# PIC24F04KA201_v01.net
KiCad netlist of a schematic drawn in EAGLE
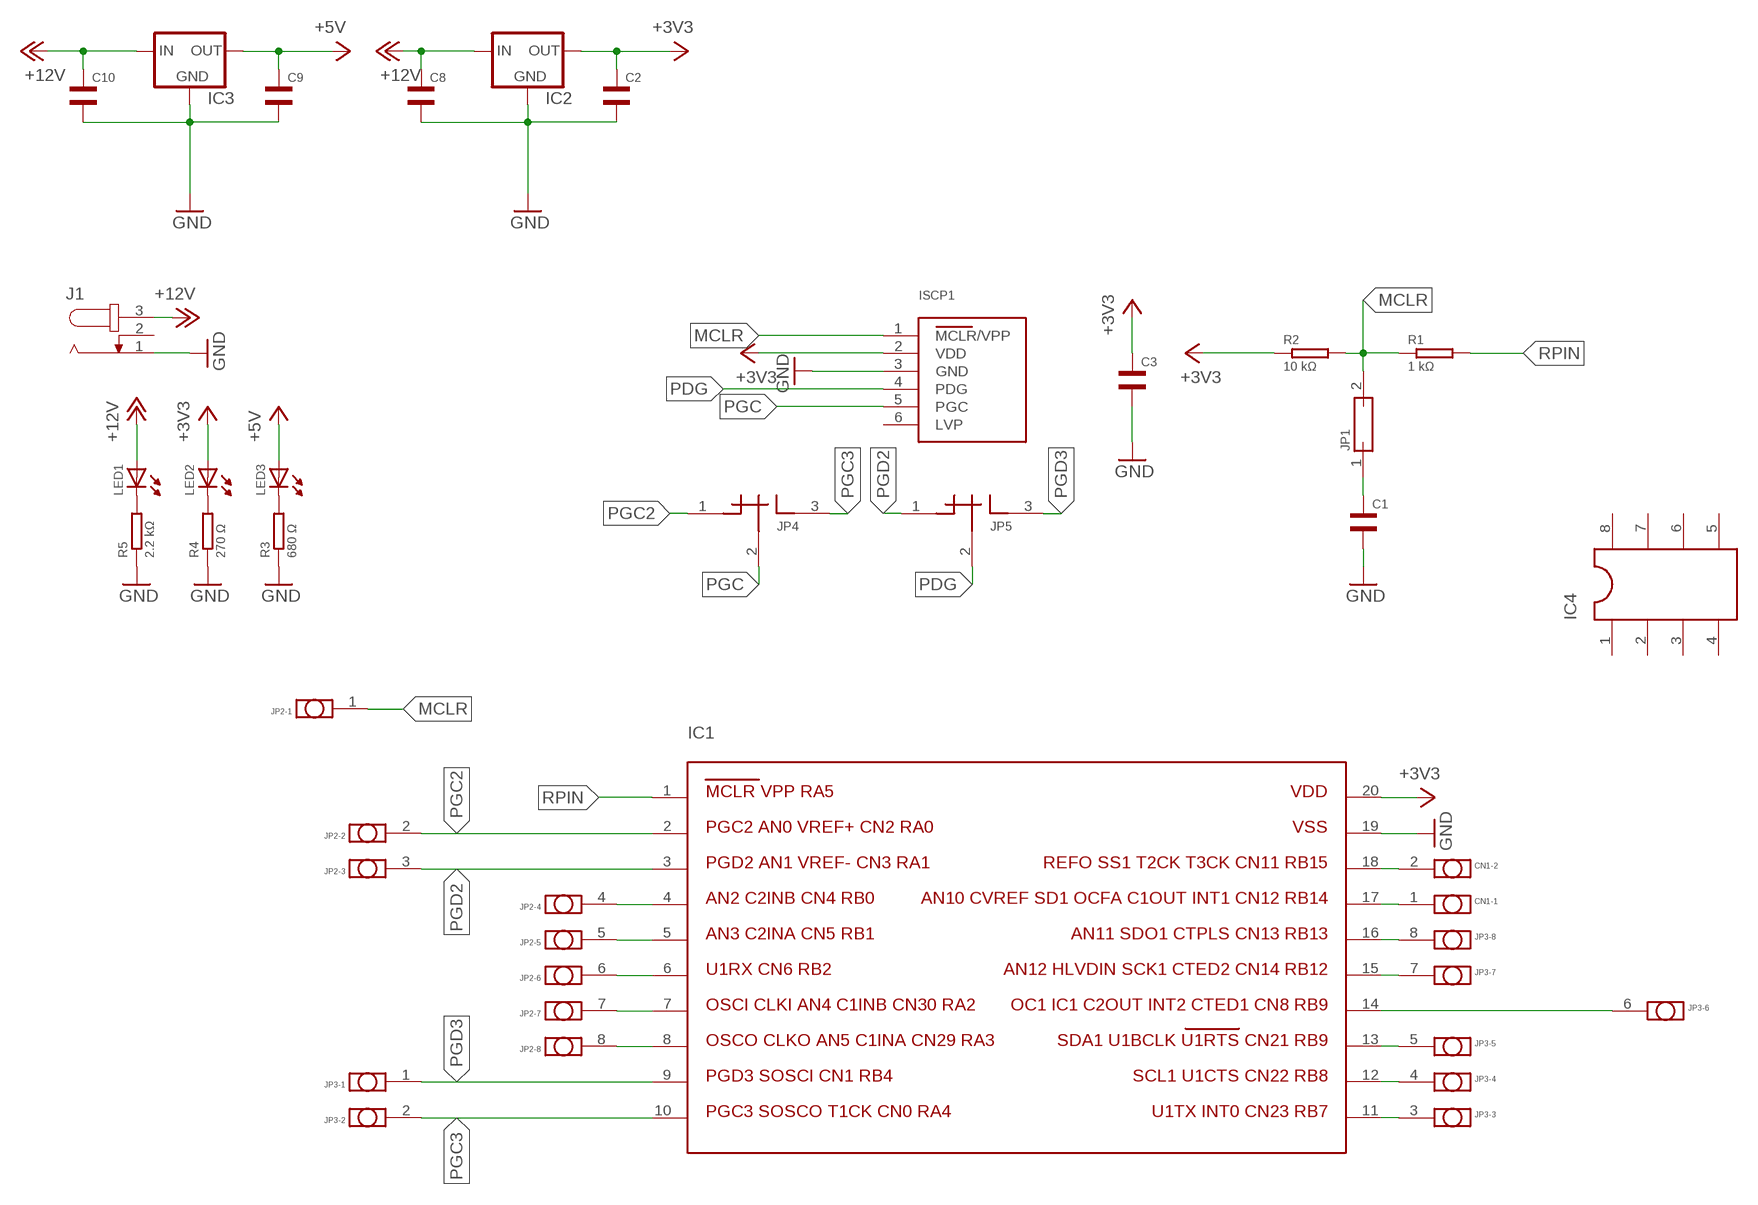
[diagram p0: schematic, sheet 1]

(export (version "E")
  (design (tool "Eeschema 10.0.6"))
  (components
    (comp (ref "C1")
      (value "CAP-SMD-0805")
      (footprint "eagle-import:SMD-0805")
      (libsource (lib "eagle-import") (part "CAP-SMD-0805"))
    )
    (comp (ref "C2")
      (value "CAP-SMD-0805")
      (footprint "eagle-import:SMD-0805")
      (libsource (lib "eagle-import") (part "CAP-SMD-0805"))
    )
    (comp (ref "C3")
      (value "CAP-SMD-0805")
      (footprint "eagle-import:SMD-0805")
      (libsource (lib "eagle-import") (part "CAP-SMD-0805"))
    )
    (comp (ref "C8")
      (value "CAP-SMD-0805")
      (footprint "eagle-import:SMD-0805")
      (libsource (lib "eagle-import") (part "CAP-SMD-0805"))
    )
    (comp (ref "C9")
      (value "CAP-SMD-0805")
      (footprint "eagle-import:SMD-0805")
      (libsource (lib "eagle-import") (part "CAP-SMD-0805"))
    )
    (comp (ref "C10")
      (value "CAP-SMD-0805")
      (footprint "eagle-import:SMD-0805")
      (libsource (lib "eagle-import") (part "CAP-SMD-0805"))
    )
    (comp (ref "CN1")
      (value "1X2")
      (footprint "eagle-import:1X2")
      (libsource (lib "eagle-import") (part "1X2"))
    )
    (comp (ref "IC1")
      (value "PIC24F04KA201")
      (footprint "eagle-import:DIP-20-SOCKET")
      (libsource (lib "eagle-import") (part "PIC24F04KA201"))
    )
    (comp (ref "IC2")
      (value "LD1117V33")
      (footprint "eagle-import:TO-220-STANDING")
      (fields (field (name "MANUFACTURER") "ST Microelectronics"))
      (libsource (lib "eagle-import") (part "LD1117V33"))
    )
    (comp (ref "IC3")
      (value "L78S05CV")
      (footprint "eagle-import:TO-220-STANDING")
      (fields (field (name "MANUFACTURER") "St Microelectronics"))
      (libsource (lib "eagle-import") (part "L78S05CV"))
    )
    (comp (ref "IC4")
      (value "DIP-08S")
      (footprint "eagle-import:DIP-08-SOCKET")
      (libsource (lib "eagle-import") (part "DIP-08S"))
    )
    (comp (ref "ISCP1")
      (value "ICSP1X6-2.54")
      (footprint "eagle-import:1X6-2.54")
      (libsource (lib "eagle-import") (part "ICSP1X6-2.54"))
    )
    (comp (ref "J1")
      (value "JACK-PLUG0")
      (footprint "eagle-import:SPC4077")
      (libsource (lib "eagle-import") (part "JACK-PLUG0"))
    )
    (comp (ref "JP1")
      (value "JP")
      (footprint "eagle-import:1X2")
      (libsource (lib "eagle-import") (part "JP"))
    )
    (comp (ref "JP2")
      (value "1X8")
      (footprint "eagle-import:1X8")
      (libsource (lib "eagle-import") (part "1X8"))
    )
    (comp (ref "JP3")
      (value "1X8")
      (footprint "eagle-import:1X8")
      (libsource (lib "eagle-import") (part "1X8"))
    )
    (comp (ref "JP4")
      (value "JP-OR")
      (footprint "eagle-import:1X3")
      (libsource (lib "eagle-import") (part "JP-OR"))
    )
    (comp (ref "JP5")
      (value "JP-OR")
      (footprint "eagle-import:1X3")
      (libsource (lib "eagle-import") (part "JP-OR"))
    )
    (comp (ref "LED1")
      (value "LED-SMD-0805")
      (footprint "eagle-import:SMD-0805")
      (libsource (lib "eagle-import") (part "LED-SMD-0805"))
    )
    (comp (ref "LED2")
      (value "LED-SMD-0805")
      (footprint "eagle-import:SMD-0805")
      (libsource (lib "eagle-import") (part "LED-SMD-0805"))
    )
    (comp (ref "LED3")
      (value "LED-SMD-0805")
      (footprint "eagle-import:SMD-0805")
      (libsource (lib "eagle-import") (part "LED-SMD-0805"))
    )
    (comp (ref "R1")
      (value "1 kΩ")
      (footprint "eagle-import:SMD-2012(0805)")
      (fields
        (field (name "MANUFACTURER") "Vishay")
        (field (name "POWER") "0.125 W")
        (field (name "TOLERANCE") "1%")
      )
      (libsource (lib "eagle-import") (part "CRCW08051K00FKTABC"))
    )
    (comp (ref "R2")
      (value "10 kΩ")
      (footprint "eagle-import:SMD-2012(0805)")
      (fields
        (field (name "MANUFACTURER") "Vishay")
        (field (name "POWER") "0.125 W")
        (field (name "TOLERANCE") "1%")
      )
      (libsource (lib "eagle-import") (part "CRCW080510K0FKTABC"))
    )
    (comp (ref "R3")
      (value "680 Ω")
      (footprint "eagle-import:SMD-2012(0805)")
      (fields (field (name "POWER") "0.125 W") (field (name "TOLERANCE") "1%"))
      (libsource (lib "eagle-import") (part "CRCW0805680RFKTABC"))
    )
    (comp (ref "R4")
      (value "270 Ω")
      (footprint "eagle-import:SMD-2012(0805)")
      (fields (field (name "POWER") "0.125 W") (field (name "TOLERANCE") "1%"))
      (libsource (lib "eagle-import") (part "CRCW0805270RFKTABC"))
    )
    (comp (ref "R5")
      (value "2.2 kΩ")
      (footprint "eagle-import:SMD-2012(0805)")
      (fields
        (field (name "MANUFACTURER") "Vishay")
        (field (name "POWER") "0.125 W")
        (field (name "TOLERANCE") "1%")
      )
      (libsource (lib "eagle-import") (part "CRCW08052K20FKTABC"))
    )
  )
  (nets
    (net (code "1") (name "+3V3") (class "Default")
      (node (ref "C2") (pin "2") (pinfunction "P$2_2") (pintype "bidirectional"))
      (node (ref "C3") (pin "2") (pinfunction "P$2_2") (pintype "bidirectional"))
      (node (ref "IC1") (pin "20") (pinfunction "P$20_20") (pintype "bidirectional"))
      (node (ref "IC2") (pin "2") (pinfunction "OUT_2") (pintype "passive"))
      (node (ref "ISCP1") (pin "2") (pinfunction "VDD_2") (pintype "bidirectional"))
      (node (ref "LED2") (pin "A") (pinfunction "A_A") (pintype "input"))
      (node (ref "R2") (pin "1") (pinfunction "P$1_1") (pintype "bidirectional"))
    )
    (net (code "2") (name "+5V") (class "Default")
      (node (ref "C9") (pin "2") (pinfunction "P$2_2") (pintype "bidirectional"))
      (node (ref "IC3") (pin "3") (pinfunction "OUT_3") (pintype "passive"))
      (node (ref "LED3") (pin "A") (pinfunction "A_A") (pintype "input"))
    )
    (net (code "3") (name "+12V") (class "Default")
      (node (ref "C10") (pin "2") (pinfunction "P$2_2") (pintype "bidirectional"))
      (node (ref "C8") (pin "2") (pinfunction "P$2_2") (pintype "bidirectional"))
      (node (ref "IC2") (pin "3") (pinfunction "IN_3") (pintype "input"))
      (node (ref "IC3") (pin "1") (pinfunction "IN_1") (pintype "input"))
      (node (ref "J1") (pin "3") (pinfunction "3_3") (pintype "passive"))
      (node (ref "LED1") (pin "A") (pinfunction "A_A") (pintype "input"))
    )
    (net (code "4") (name "GND") (class "Default")
      (node (ref "C1") (pin "1") (pinfunction "P$1_1") (pintype "bidirectional"))
      (node (ref "C10") (pin "1") (pinfunction "P$1_1") (pintype "bidirectional"))
      (node (ref "C2") (pin "1") (pinfunction "P$1_1") (pintype "bidirectional"))
      (node (ref "C3") (pin "1") (pinfunction "P$1_1") (pintype "bidirectional"))
      (node (ref "C8") (pin "1") (pinfunction "P$1_1") (pintype "bidirectional"))
      (node (ref "C9") (pin "1") (pinfunction "P$1_1") (pintype "bidirectional"))
      (node (ref "IC1") (pin "19") (pinfunction "P$19_19") (pintype "bidirectional"))
      (node (ref "IC2") (pin "1") (pinfunction "GND_1") (pintype "input"))
      (node (ref "IC3") (pin "2") (pinfunction "GND_2") (pintype "input"))
      (node (ref "ISCP1") (pin "3") (pinfunction "GND_3") (pintype "bidirectional"))
      (node (ref "J1") (pin "1") (pinfunction "1_1") (pintype "passive"))
      (node (ref "R3") (pin "1") (pinfunction "P$1_1") (pintype "bidirectional"))
      (node (ref "R4") (pin "1") (pinfunction "P$1_1") (pintype "bidirectional"))
      (node (ref "R5") (pin "1") (pinfunction "P$1_1") (pintype "bidirectional"))
    )
    (net (code "5") (name "MCLR") (class "Default")
      (node (ref "ISCP1") (pin "1") (pinfunction "MCLR/VPP_1") (pintype "bidirectional"))
      (node (ref "JP1") (pin "2") (pinfunction "P$2_2") (pintype "bidirectional"))
      (node (ref "JP2") (pin "1") (pinfunction "P$1_1") (pintype "bidirectional"))
      (node (ref "R1") (pin "1") (pinfunction "P$1_1") (pintype "bidirectional"))
      (node (ref "R2") (pin "2") (pinfunction "P$2_2") (pintype "bidirectional"))
    )
    (net (code "6") (name "Net-(C1-P$2)") (class "Default")
      (node (ref "C1") (pin "2") (pinfunction "P$2_2") (pintype "bidirectional"))
      (node (ref "JP1") (pin "1") (pinfunction "P$1_1") (pintype "bidirectional"))
    )
    (net (code "7") (name "Net-(CN1A-P$1)") (class "Default")
      (node (ref "CN1") (pin "1") (pinfunction "P$1_1") (pintype "bidirectional"))
      (node (ref "IC1") (pin "17") (pinfunction "P$17_17") (pintype "bidirectional"))
    )
    (net (code "8") (name "Net-(CN1B-P$1)") (class "Default")
      (node (ref "CN1") (pin "2") (pinfunction "P$1_2") (pintype "bidirectional"))
      (node (ref "IC1") (pin "18") (pinfunction "P$18_18") (pintype "bidirectional"))
    )
    (net (code "9") (name "Net-(IC1-P$4)") (class "Default")
      (node (ref "IC1") (pin "4") (pinfunction "P$4_4") (pintype "bidirectional"))
      (node (ref "JP2") (pin "4") (pinfunction "P$1_4") (pintype "bidirectional"))
    )
    (net (code "10") (name "Net-(IC1-P$5)") (class "Default")
      (node (ref "IC1") (pin "5") (pinfunction "P$5_5") (pintype "bidirectional"))
      (node (ref "JP2") (pin "5") (pinfunction "P$1_5") (pintype "bidirectional"))
    )
    (net (code "11") (name "Net-(IC1-P$6)") (class "Default")
      (node (ref "IC1") (pin "6") (pinfunction "P$6_6") (pintype "bidirectional"))
      (node (ref "JP2") (pin "6") (pinfunction "P$1_6") (pintype "bidirectional"))
    )
    (net (code "12") (name "Net-(IC1-P$7)") (class "Default")
      (node (ref "IC1") (pin "7") (pinfunction "P$7_7") (pintype "bidirectional"))
      (node (ref "JP2") (pin "7") (pinfunction "P$1_7") (pintype "bidirectional"))
    )
    (net (code "13") (name "Net-(IC1-P$8)") (class "Default")
      (node (ref "IC1") (pin "8") (pinfunction "P$8_8") (pintype "bidirectional"))
      (node (ref "JP2") (pin "8") (pinfunction "P$1_8") (pintype "bidirectional"))
    )
    (net (code "14") (name "Net-(IC1-P$11)") (class "Default")
      (node (ref "IC1") (pin "11") (pinfunction "P$11_11") (pintype "bidirectional"))
      (node (ref "JP3") (pin "3") (pinfunction "P$1_3") (pintype "bidirectional"))
    )
    (net (code "15") (name "Net-(IC1-P$12)") (class "Default")
      (node (ref "IC1") (pin "12") (pinfunction "P$12_12") (pintype "bidirectional"))
      (node (ref "JP3") (pin "4") (pinfunction "P$1_4") (pintype "bidirectional"))
    )
    (net (code "16") (name "Net-(IC1-P$13)") (class "Default")
      (node (ref "IC1") (pin "13") (pinfunction "P$13_13") (pintype "bidirectional"))
      (node (ref "JP3") (pin "5") (pinfunction "P$1_5") (pintype "bidirectional"))
    )
    (net (code "17") (name "Net-(IC1-P$14)") (class "Default")
      (node (ref "IC1") (pin "14") (pinfunction "P$14_14") (pintype "bidirectional"))
      (node (ref "JP3") (pin "6") (pinfunction "P$1_6") (pintype "bidirectional"))
    )
    (net (code "18") (name "Net-(IC1-P$15)") (class "Default")
      (node (ref "IC1") (pin "15") (pinfunction "P$15_15") (pintype "bidirectional"))
      (node (ref "JP3") (pin "7") (pinfunction "P$1_7") (pintype "bidirectional"))
    )
    (net (code "19") (name "Net-(IC1-P$16)") (class "Default")
      (node (ref "IC1") (pin "16") (pinfunction "P$16_16") (pintype "bidirectional"))
      (node (ref "JP3") (pin "8") (pinfunction "P$1_8") (pintype "bidirectional"))
    )
    (net (code "20") (name "Net-(R3-P$2)") (class "Default")
      (node (ref "LED3") (pin "C") (pinfunction "C_C") (pintype "output"))
      (node (ref "R3") (pin "2") (pinfunction "P$2_2") (pintype "bidirectional"))
    )
    (net (code "21") (name "Net-(R4-P$2)") (class "Default")
      (node (ref "LED2") (pin "C") (pinfunction "C_C") (pintype "output"))
      (node (ref "R4") (pin "2") (pinfunction "P$2_2") (pintype "bidirectional"))
    )
    (net (code "22") (name "Net-(R5-P$2)") (class "Default")
      (node (ref "LED1") (pin "C") (pinfunction "C_C") (pintype "output"))
      (node (ref "R5") (pin "2") (pinfunction "P$2_2") (pintype "bidirectional"))
    )
    (net (code "23") (name "PDG") (class "Default")
      (node (ref "ISCP1") (pin "4") (pinfunction "PDG_4") (pintype "bidirectional"))
      (node (ref "JP5") (pin "2") (pinfunction "P$3_2") (pintype "bidirectional"))
    )
    (net (code "24") (name "PGC") (class "Default")
      (node (ref "ISCP1") (pin "5") (pinfunction "PGC_5") (pintype "bidirectional"))
      (node (ref "JP4") (pin "2") (pinfunction "P$3_2") (pintype "bidirectional"))
    )
    (net (code "25") (name "PGC2") (class "Default")
      (node (ref "IC1") (pin "2") (pinfunction "P$2_2") (pintype "bidirectional"))
      (node (ref "JP2") (pin "2") (pinfunction "P$1_2") (pintype "bidirectional"))
      (node (ref "JP4") (pin "1") (pinfunction "P$1_1") (pintype "bidirectional"))
    )
    (net (code "26") (name "PGC3") (class "Default")
      (node (ref "IC1") (pin "10") (pinfunction "P$10_10") (pintype "bidirectional"))
      (node (ref "JP3") (pin "2") (pinfunction "P$1_2") (pintype "bidirectional"))
      (node (ref "JP4") (pin "3") (pinfunction "P$2_3") (pintype "bidirectional"))
    )
    (net (code "27") (name "PGD2") (class "Default")
      (node (ref "IC1") (pin "3") (pinfunction "P$3_3") (pintype "bidirectional"))
      (node (ref "JP2") (pin "3") (pinfunction "P$1_3") (pintype "bidirectional"))
      (node (ref "JP5") (pin "1") (pinfunction "P$1_1") (pintype "bidirectional"))
    )
    (net (code "28") (name "PGD3") (class "Default")
      (node (ref "IC1") (pin "9") (pinfunction "P$9_9") (pintype "bidirectional"))
      (node (ref "JP3") (pin "1") (pinfunction "P$1_1") (pintype "bidirectional"))
      (node (ref "JP5") (pin "3") (pinfunction "P$2_3") (pintype "bidirectional"))
    )
    (net (code "29") (name "RPIN") (class "Default")
      (node (ref "IC1") (pin "1") (pinfunction "P$1_1") (pintype "bidirectional"))
      (node (ref "R1") (pin "2") (pinfunction "P$2_2") (pintype "bidirectional"))
    )
    (net (code "30") (name "unconnected-(IC4-Pad1)") (class "Default")
      (node (ref "IC4") (pin "1") (pinfunction "1_1") (pintype "passive"))
    )
    (net (code "31") (name "unconnected-(IC4-Pad2)") (class "Default")
      (node (ref "IC4") (pin "2") (pinfunction "2_2") (pintype "passive"))
    )
    (net (code "32") (name "unconnected-(IC4-Pad3)") (class "Default")
      (node (ref "IC4") (pin "3") (pinfunction "3_3") (pintype "passive"))
    )
    (net (code "33") (name "unconnected-(IC4-Pad4)") (class "Default")
      (node (ref "IC4") (pin "4") (pinfunction "4_4") (pintype "passive"))
    )
    (net (code "34") (name "unconnected-(IC4-Pad5)") (class "Default")
      (node (ref "IC4") (pin "5") (pinfunction "5_5") (pintype "passive"))
    )
    (net (code "35") (name "unconnected-(IC4-Pad6)") (class "Default")
      (node (ref "IC4") (pin "6") (pinfunction "6_6") (pintype "passive"))
    )
    (net (code "36") (name "unconnected-(IC4-Pad7)") (class "Default")
      (node (ref "IC4") (pin "7") (pinfunction "7_7") (pintype "passive"))
    )
    (net (code "37") (name "unconnected-(IC4-Pad8)") (class "Default")
      (node (ref "IC4") (pin "8") (pinfunction "8_8") (pintype "passive"))
    )
    (net (code "38") (name "unconnected-(ISCP1-LVP-Pad6)") (class "Default")
      (node (ref "ISCP1") (pin "6") (pinfunction "LVP_6") (pintype "bidirectional"))
    )
    (net (code "39") (name "unconnected-(J1-Pad2)") (class "Default")
      (node (ref "J1") (pin "2") (pinfunction "2_2") (pintype "passive"))
    )
  )
)
